# STC12C5A_LQFP44_Mini.net
KiCad netlist of a schematic drawn in Altium Designer
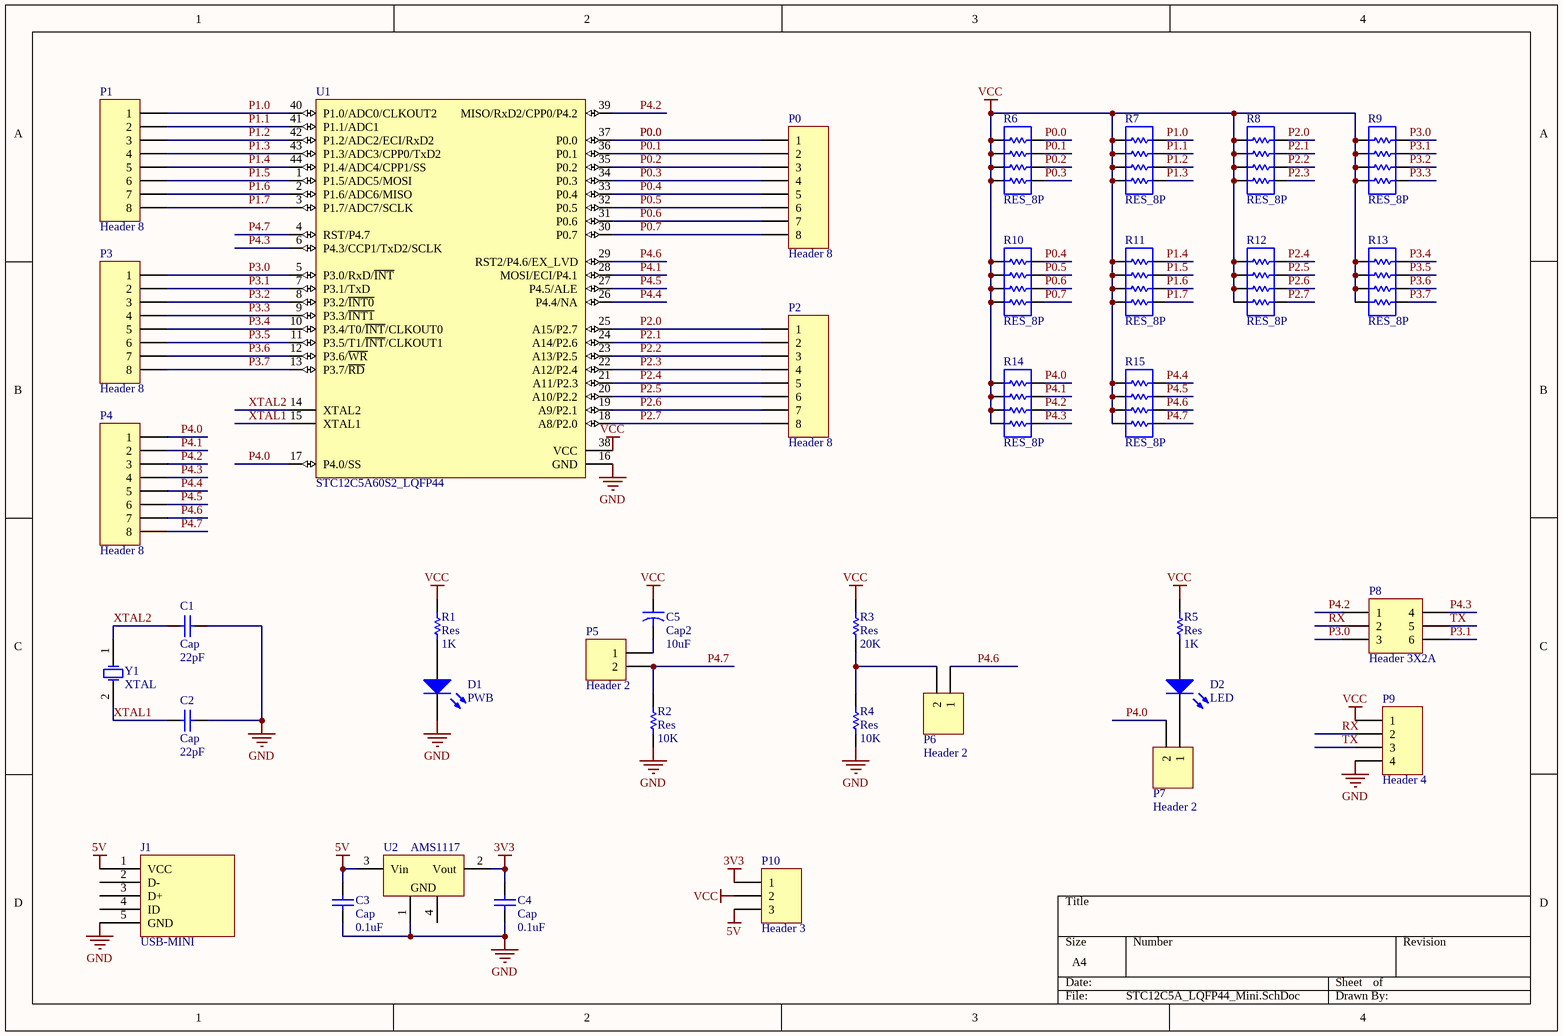
[diagram p0: STC12C5A_LQFP44_Mini.SchDoc]

(export (version "E")
  (design (tool "Eeschema 10.0.6"))
  (components
    (comp (ref "C1")
      (value "Cap")
      (footprint "C0805")
      (description "Capacitor")
      (fields (field (name "ALTIUM_VALUE") "22pF") (field (name "PUBLISHER") "Altium Limited"))
      (libsource (lib "Devices") (part "Cap"))
    )
    (comp (ref "C2")
      (value "Cap")
      (footprint "C0805")
      (description "Capacitor")
      (fields (field (name "ALTIUM_VALUE") "22pF") (field (name "PUBLISHER") "Altium Limited"))
      (libsource (lib "Devices") (part "Cap"))
    )
    (comp (ref "C3")
      (value "Cap")
      (footprint "C0805")
      (description "Capacitor")
      (fields (field (name "ALTIUM_VALUE") "0.1uF") (field (name "PUBLISHER") "Altium Limited"))
      (libsource (lib "Devices") (part "Cap"))
    )
    (comp (ref "C4")
      (value "Cap")
      (footprint "C0805")
      (description "Capacitor")
      (fields (field (name "ALTIUM_VALUE") "0.1uF") (field (name "PUBLISHER") "Altium Limited"))
      (libsource (lib "Devices") (part "Cap"))
    )
    (comp (ref "C5")
      (value "Cap2")
      (footprint "CAP-4.2")
      (description "Capacitor")
      (fields (field (name "ALTIUM_VALUE") "10uF") (field (name "PUBLISHER") "Altium Limited"))
      (libsource (lib "Devices") (part "Cap2"))
    )
    (comp (ref "D1")
      (value "PWB")
      (footprint "C0805")
      (description "发光二极管")
      (libsource (lib "Devices") (part "LED-2P"))
    )
    (comp (ref "D2")
      (value "LED")
      (footprint "C0805")
      (description "发光二极管")
      (libsource (lib "Devices") (part "LED-2P"))
    )
    (comp (ref "J1")
      (value "USB-MINI")
      (footprint "USB-MINI-A-SM")
      (libsource (lib "Connectors") (part "USB-MINI"))
    )
    (comp (ref "P0")
      (value "Header 8")
      (footprint "HDR1X8")
      (description "Header, 8-Pin")
      (fields (field (name "PUBLISHER") "Altium Limited"))
      (libsource (lib "") (part "Header 8_1"))
    )
    (comp (ref "P1")
      (value "Header 8")
      (footprint "HDR1X8")
      (description "Header, 8-Pin")
      (fields (field (name "PUBLISHER") "Altium Limited"))
      (libsource (lib "Connectors") (part "Header 8"))
    )
    (comp (ref "P2")
      (value "Header 8")
      (footprint "HDR1X8")
      (description "Header, 8-Pin")
      (fields (field (name "PUBLISHER") "Altium Limited"))
      (libsource (lib "") (part "Header 8_1"))
    )
    (comp (ref "P3")
      (value "Header 8")
      (footprint "HDR1X8")
      (description "Header, 8-Pin")
      (fields (field (name "PUBLISHER") "Altium Limited"))
      (libsource (lib "Connectors") (part "Header 8"))
    )
    (comp (ref "P4")
      (value "Header 8")
      (footprint "HDR1X8")
      (description "Header, 8-Pin")
      (fields (field (name "PUBLISHER") "Altium Limited"))
      (libsource (lib "Connectors") (part "Header 8"))
    )
    (comp (ref "P5")
      (value "Header 2")
      (footprint "HDR1X2")
      (description "Header, 2-Pin")
      (fields (field (name "PUBLISHER") "Altium Limited"))
      (libsource (lib "Connectors") (part "Header 2"))
    )
    (comp (ref "P6")
      (value "Header 2")
      (footprint "HDR1X2")
      (description "Header, 2-Pin")
      (fields (field (name "PUBLISHER") "Altium Limited"))
      (libsource (lib "Connectors") (part "Header 2"))
    )
    (comp (ref "P7")
      (value "Header 2")
      (footprint "HDR1X2")
      (description "Header, 2-Pin")
      (fields (field (name "PUBLISHER") "Altium Limited"))
      (libsource (lib "Connectors") (part "Header 2"))
    )
    (comp (ref "P8")
      (value "Header 3X2A")
      (footprint "HDR2X3_CEN")
      (description "Header, 3-Pin, Dual row")
      (fields (field (name "PUBLISHER") "Altium Limited"))
      (libsource (lib "Connectors") (part "Header 3X2A"))
    )
    (comp (ref "P9")
      (value "Header 4")
      (footprint "HDR1X4")
      (description "Header, 4-Pin")
      (fields (field (name "PUBLISHER") "Altium Limited"))
      (libsource (lib "Connectors") (part "Header 4"))
    )
    (comp (ref "P10")
      (value "Header 3")
      (footprint "HDR1X3")
      (description "Header, 3-Pin")
      (fields (field (name "PUBLISHER") "Altium Limited"))
      (libsource (lib "Connectors") (part "Header 3"))
    )
    (comp (ref "R1")
      (value "Res")
      (footprint "0805")
      (description "Resistor")
      (fields (field (name "ALTIUM_VALUE") "1K") (field (name "PUBLISHER") "Altium Limited"))
      (libsource (lib "Devices") (part "Res"))
    )
    (comp (ref "R2")
      (value "Res")
      (footprint "0805")
      (description "Resistor")
      (fields (field (name "ALTIUM_VALUE") "10K") (field (name "PUBLISHER") "Altium Limited"))
      (libsource (lib "Devices") (part "Res"))
    )
    (comp (ref "R3")
      (value "Res")
      (footprint "0805")
      (description "Resistor")
      (fields (field (name "ALTIUM_VALUE") "20K") (field (name "PUBLISHER") "Altium Limited"))
      (libsource (lib "Devices") (part "Res"))
    )
    (comp (ref "R4")
      (value "Res")
      (footprint "0805")
      (description "Resistor")
      (fields (field (name "ALTIUM_VALUE") "10K") (field (name "PUBLISHER") "Altium Limited"))
      (libsource (lib "Devices") (part "Res"))
    )
    (comp (ref "R5")
      (value "Res")
      (footprint "0805")
      (description "Resistor")
      (fields (field (name "ALTIUM_VALUE") "1K") (field (name "PUBLISHER") "Altium Limited"))
      (libsource (lib "Devices") (part "Res"))
    )
    (comp (ref "R6")
      (value "RES_8P")
      (footprint "RES_8P_0603")
      (description "贴片排阻")
      (libsource (lib "Devices") (part "RES_8P"))
    )
    (comp (ref "R7")
      (value "RES_8P")
      (footprint "RES_8P_0603")
      (description "贴片排阻")
      (libsource (lib "Devices") (part "RES_8P"))
    )
    (comp (ref "R8")
      (value "RES_8P")
      (footprint "RES_8P_0603")
      (description "贴片排阻")
      (libsource (lib "Devices") (part "RES_8P"))
    )
    (comp (ref "R9")
      (value "RES_8P")
      (footprint "RES_8P_0603")
      (description "贴片排阻")
      (libsource (lib "Devices") (part "RES_8P"))
    )
    (comp (ref "R10")
      (value "RES_8P")
      (footprint "RES_8P_0603")
      (description "贴片排阻")
      (libsource (lib "Devices") (part "RES_8P"))
    )
    (comp (ref "R11")
      (value "RES_8P")
      (footprint "RES_8P_0603")
      (description "贴片排阻")
      (libsource (lib "Devices") (part "RES_8P"))
    )
    (comp (ref "R12")
      (value "RES_8P")
      (footprint "RES_8P_0603")
      (description "贴片排阻")
      (libsource (lib "Devices") (part "RES_8P"))
    )
    (comp (ref "R13")
      (value "RES_8P")
      (footprint "RES_8P_0603")
      (description "贴片排阻")
      (libsource (lib "Devices") (part "RES_8P"))
    )
    (comp (ref "R14")
      (value "RES_8P")
      (footprint "RES_8P_0603")
      (description "贴片排阻")
      (libsource (lib "Devices") (part "RES_8P"))
    )
    (comp (ref "R15")
      (value "RES_8P")
      (footprint "RES_8P_0603")
      (description "贴片排阻")
      (libsource (lib "Devices") (part "RES_8P"))
    )
    (comp (ref "U1")
      (value "STC12C5A60S2_LQFP44")
      (footprint "LQFP44")
      (description "增强型8051单片机")
      (libsource (lib "STC") (part "STC12C5A60S2_LQFP44"))
    )
    (comp (ref "U2")
      (value "AMS1117")
      (footprint "SOT-223")
      (description "低压稳压器-1A")
      (libsource (lib "IC") (part "AMS1117"))
    )
    (comp (ref "Y1")
      (value "XTAL")
      (footprint "XTAL1")
      (description "Crystal Oscillator")
      (fields (field (name "PUBLISHER") "Altium Limited"))
      (libsource (lib "Miscellaneous Devices") (part "XTAL"))
    )
  )
  (nets
    (net (code "1") (name "/P0.0") (class "Default")
      (node (ref "P0") (pin "1") (pinfunction "1_1") (pintype "passive"))
      (node (ref "R6") (pin "2") (pinfunction "2_2") (pintype "passive"))
      (node (ref "U1") (pin "37") (pinfunction "P0.0_37") (pintype "bidirectional"))
    )
    (net (code "2") (name "/P0.1") (class "Default")
      (node (ref "P0") (pin "2") (pinfunction "2_2") (pintype "passive"))
      (node (ref "R6") (pin "4") (pinfunction "4_4") (pintype "passive"))
      (node (ref "U1") (pin "36") (pinfunction "P0.1_36") (pintype "bidirectional"))
    )
    (net (code "3") (name "/P0.2") (class "Default")
      (node (ref "P0") (pin "3") (pinfunction "3_3") (pintype "passive"))
      (node (ref "R6") (pin "6") (pinfunction "6_6") (pintype "passive"))
      (node (ref "U1") (pin "35") (pinfunction "P0.2_35") (pintype "bidirectional"))
    )
    (net (code "4") (name "/P0.3") (class "Default")
      (node (ref "P0") (pin "4") (pinfunction "4_4") (pintype "passive"))
      (node (ref "R6") (pin "8") (pinfunction "8_8") (pintype "passive"))
      (node (ref "U1") (pin "34") (pinfunction "P0.3_34") (pintype "bidirectional"))
    )
    (net (code "5") (name "/P0.4") (class "Default")
      (node (ref "P0") (pin "5") (pinfunction "5_5") (pintype "passive"))
      (node (ref "R10") (pin "2") (pinfunction "2_2") (pintype "passive"))
      (node (ref "U1") (pin "33") (pinfunction "P0.4_33") (pintype "bidirectional"))
    )
    (net (code "6") (name "/P0.5") (class "Default")
      (node (ref "P0") (pin "6") (pinfunction "6_6") (pintype "passive"))
      (node (ref "R10") (pin "4") (pinfunction "4_4") (pintype "passive"))
      (node (ref "U1") (pin "32") (pinfunction "P0.5_32") (pintype "bidirectional"))
    )
    (net (code "7") (name "/P0.6") (class "Default")
      (node (ref "P0") (pin "7") (pinfunction "7_7") (pintype "passive"))
      (node (ref "R10") (pin "6") (pinfunction "6_6") (pintype "passive"))
      (node (ref "U1") (pin "31") (pinfunction "P0.6_31") (pintype "bidirectional"))
    )
    (net (code "8") (name "/P0.7") (class "Default")
      (node (ref "P0") (pin "8") (pinfunction "8_8") (pintype "passive"))
      (node (ref "R10") (pin "8") (pinfunction "8_8") (pintype "passive"))
      (node (ref "U1") (pin "30") (pinfunction "P0.7_30") (pintype "bidirectional"))
    )
    (net (code "9") (name "/P1.0") (class "Default")
      (node (ref "P1") (pin "1") (pinfunction "1_1") (pintype "passive"))
      (node (ref "R7") (pin "2") (pinfunction "2_2") (pintype "passive"))
      (node (ref "U1") (pin "40") (pinfunction "P1.0/ADC0/CLKOUT2_40") (pintype "bidirectional"))
    )
    (net (code "10") (name "/P1.1") (class "Default")
      (node (ref "P1") (pin "2") (pinfunction "2_2") (pintype "passive"))
      (node (ref "R7") (pin "4") (pinfunction "4_4") (pintype "passive"))
      (node (ref "U1") (pin "41") (pinfunction "P1.1/ADC1_41") (pintype "bidirectional"))
    )
    (net (code "11") (name "/P1.2") (class "Default")
      (node (ref "P1") (pin "3") (pinfunction "3_3") (pintype "passive"))
      (node (ref "R7") (pin "6") (pinfunction "6_6") (pintype "passive"))
      (node (ref "U1") (pin "42") (pinfunction "P1.2/ADC2/ECI/RxD2_42") (pintype "bidirectional"))
    )
    (net (code "12") (name "/P1.3") (class "Default")
      (node (ref "P1") (pin "4") (pinfunction "4_4") (pintype "passive"))
      (node (ref "R7") (pin "8") (pinfunction "8_8") (pintype "passive"))
      (node (ref "U1") (pin "43") (pinfunction "P1.3/ADC3/CPP0/TxD2_43") (pintype "bidirectional"))
    )
    (net (code "13") (name "/P1.4") (class "Default")
      (node (ref "P1") (pin "5") (pinfunction "5_5") (pintype "passive"))
      (node (ref "R11") (pin "2") (pinfunction "2_2") (pintype "passive"))
      (node (ref "U1") (pin "44") (pinfunction "P1.4/ADC4/CPP1/SS_44") (pintype "bidirectional"))
    )
    (net (code "14") (name "/P1.5") (class "Default")
      (node (ref "P1") (pin "6") (pinfunction "6_6") (pintype "passive"))
      (node (ref "R11") (pin "4") (pinfunction "4_4") (pintype "passive"))
      (node (ref "U1") (pin "1") (pinfunction "P1.5/ADC5/MOSI_1") (pintype "bidirectional"))
    )
    (net (code "15") (name "/P1.6") (class "Default")
      (node (ref "P1") (pin "7") (pinfunction "7_7") (pintype "passive"))
      (node (ref "R11") (pin "6") (pinfunction "6_6") (pintype "passive"))
      (node (ref "U1") (pin "2") (pinfunction "P1.6/ADC6/MISO_2") (pintype "bidirectional"))
    )
    (net (code "16") (name "/P1.7") (class "Default")
      (node (ref "P1") (pin "8") (pinfunction "8_8") (pintype "passive"))
      (node (ref "R11") (pin "8") (pinfunction "8_8") (pintype "passive"))
      (node (ref "U1") (pin "3") (pinfunction "P1.7/ADC7/SCLK_3") (pintype "bidirectional"))
    )
    (net (code "17") (name "/P2.0") (class "Default")
      (node (ref "P2") (pin "1") (pinfunction "1_1") (pintype "passive"))
      (node (ref "R8") (pin "2") (pinfunction "2_2") (pintype "passive"))
      (node (ref "U1") (pin "25") (pinfunction "A15/P2.7_25") (pintype "bidirectional"))
    )
    (net (code "18") (name "/P2.1") (class "Default")
      (node (ref "P2") (pin "2") (pinfunction "2_2") (pintype "passive"))
      (node (ref "R8") (pin "4") (pinfunction "4_4") (pintype "passive"))
      (node (ref "U1") (pin "24") (pinfunction "A14/P2.6_24") (pintype "bidirectional"))
    )
    (net (code "19") (name "/P2.2") (class "Default")
      (node (ref "P2") (pin "3") (pinfunction "3_3") (pintype "passive"))
      (node (ref "R8") (pin "6") (pinfunction "6_6") (pintype "passive"))
      (node (ref "U1") (pin "23") (pinfunction "A13/P2.5_23") (pintype "bidirectional"))
    )
    (net (code "20") (name "/P2.3") (class "Default")
      (node (ref "P2") (pin "4") (pinfunction "4_4") (pintype "passive"))
      (node (ref "R8") (pin "8") (pinfunction "8_8") (pintype "passive"))
      (node (ref "U1") (pin "22") (pinfunction "A12/P2.4_22") (pintype "bidirectional"))
    )
    (net (code "21") (name "/P2.4") (class "Default")
      (node (ref "P2") (pin "5") (pinfunction "5_5") (pintype "passive"))
      (node (ref "R12") (pin "2") (pinfunction "2_2") (pintype "passive"))
      (node (ref "U1") (pin "21") (pinfunction "A11/P2.3_21") (pintype "bidirectional"))
    )
    (net (code "22") (name "/P2.5") (class "Default")
      (node (ref "P2") (pin "6") (pinfunction "6_6") (pintype "passive"))
      (node (ref "R12") (pin "4") (pinfunction "4_4") (pintype "passive"))
      (node (ref "U1") (pin "20") (pinfunction "A10/P2.2_20") (pintype "bidirectional"))
    )
    (net (code "23") (name "/P2.6") (class "Default")
      (node (ref "P2") (pin "7") (pinfunction "7_7") (pintype "passive"))
      (node (ref "R12") (pin "6") (pinfunction "6_6") (pintype "passive"))
      (node (ref "U1") (pin "19") (pinfunction "A9/P2.1_19") (pintype "bidirectional"))
    )
    (net (code "24") (name "/P2.7") (class "Default")
      (node (ref "P2") (pin "8") (pinfunction "8_8") (pintype "passive"))
      (node (ref "R12") (pin "8") (pinfunction "8_8") (pintype "passive"))
      (node (ref "U1") (pin "18") (pinfunction "A8/P2.0_18") (pintype "bidirectional"))
    )
    (net (code "25") (name "/P3.0") (class "Default")
      (node (ref "P3") (pin "1") (pinfunction "1_1") (pintype "passive"))
      (node (ref "P8") (pin "3") (pinfunction "3_3") (pintype "passive"))
      (node (ref "R9") (pin "2") (pinfunction "2_2") (pintype "passive"))
      (node (ref "U1") (pin "5") (pinfunction "P3.0/RxD/~{INT}_5") (pintype "bidirectional"))
    )
    (net (code "26") (name "/P3.1") (class "Default")
      (node (ref "P3") (pin "2") (pinfunction "2_2") (pintype "passive"))
      (node (ref "P8") (pin "6") (pinfunction "6_6") (pintype "passive"))
      (node (ref "R9") (pin "4") (pinfunction "4_4") (pintype "passive"))
      (node (ref "U1") (pin "7") (pinfunction "P3.1/TxD_7") (pintype "bidirectional"))
    )
    (net (code "27") (name "/P3.2") (class "Default")
      (node (ref "P3") (pin "3") (pinfunction "3_3") (pintype "passive"))
      (node (ref "R9") (pin "6") (pinfunction "6_6") (pintype "passive"))
      (node (ref "U1") (pin "8") (pinfunction "P3.2/~{INT0}_8") (pintype "bidirectional"))
    )
    (net (code "28") (name "/P3.3") (class "Default")
      (node (ref "P3") (pin "4") (pinfunction "4_4") (pintype "passive"))
      (node (ref "R9") (pin "8") (pinfunction "8_8") (pintype "passive"))
      (node (ref "U1") (pin "9") (pinfunction "P3.3/~{INT1}_9") (pintype "bidirectional"))
    )
    (net (code "29") (name "/P3.4") (class "Default")
      (node (ref "P3") (pin "5") (pinfunction "5_5") (pintype "passive"))
      (node (ref "R13") (pin "2") (pinfunction "2_2") (pintype "passive"))
      (node (ref "U1") (pin "10") (pinfunction "P3.4/T0/~{INT}/CLKOUT0_10") (pintype "bidirectional"))
    )
    (net (code "30") (name "/P3.5") (class "Default")
      (node (ref "P3") (pin "6") (pinfunction "6_6") (pintype "passive"))
      (node (ref "R13") (pin "4") (pinfunction "4_4") (pintype "passive"))
      (node (ref "U1") (pin "11") (pinfunction "P3.5/T1/~{INT}/CLKOUT1_11") (pintype "bidirectional"))
    )
    (net (code "31") (name "/P3.6") (class "Default")
      (node (ref "P3") (pin "7") (pinfunction "7_7") (pintype "passive"))
      (node (ref "R13") (pin "6") (pinfunction "6_6") (pintype "passive"))
      (node (ref "U1") (pin "12") (pinfunction "P3.6/~{WR}_12") (pintype "bidirectional"))
    )
    (net (code "32") (name "/P3.7") (class "Default")
      (node (ref "P3") (pin "8") (pinfunction "8_8") (pintype "passive"))
      (node (ref "R13") (pin "8") (pinfunction "8_8") (pintype "passive"))
      (node (ref "U1") (pin "13") (pinfunction "P3.7/~{RD}_13") (pintype "bidirectional"))
    )
    (net (code "33") (name "/P4.0") (class "Default")
      (node (ref "P4") (pin "1") (pinfunction "1_1") (pintype "passive"))
      (node (ref "P7") (pin "2") (pinfunction "2_2") (pintype "passive"))
      (node (ref "R14") (pin "2") (pinfunction "2_2") (pintype "passive"))
      (node (ref "U1") (pin "17") (pinfunction "P4.0/SS_17") (pintype "bidirectional"))
    )
    (net (code "34") (name "/P4.1") (class "Default")
      (node (ref "P4") (pin "2") (pinfunction "2_2") (pintype "passive"))
      (node (ref "R14") (pin "4") (pinfunction "4_4") (pintype "passive"))
      (node (ref "U1") (pin "28") (pinfunction "MOSI/ECI/P4.1_28") (pintype "bidirectional"))
    )
    (net (code "35") (name "/P4.2") (class "Default")
      (node (ref "P4") (pin "3") (pinfunction "3_3") (pintype "passive"))
      (node (ref "P8") (pin "1") (pinfunction "1_1") (pintype "passive"))
      (node (ref "R14") (pin "6") (pinfunction "6_6") (pintype "passive"))
      (node (ref "U1") (pin "39") (pinfunction "MISO/RxD2/CPP0/P4.2_39") (pintype "bidirectional"))
    )
    (net (code "36") (name "/P4.3") (class "Default")
      (node (ref "P4") (pin "4") (pinfunction "4_4") (pintype "passive"))
      (node (ref "P8") (pin "4") (pinfunction "4_4") (pintype "passive"))
      (node (ref "R14") (pin "8") (pinfunction "8_8") (pintype "passive"))
      (node (ref "U1") (pin "6") (pinfunction "P4.3/CCP1/TxD2/SCLK_6") (pintype "bidirectional"))
    )
    (net (code "37") (name "/P4.4") (class "Default")
      (node (ref "P4") (pin "5") (pinfunction "5_5") (pintype "passive"))
      (node (ref "R15") (pin "2") (pinfunction "2_2") (pintype "passive"))
      (node (ref "U1") (pin "26") (pinfunction "P4.4/NA_26") (pintype "bidirectional"))
    )
    (net (code "38") (name "/P4.5") (class "Default")
      (node (ref "P4") (pin "6") (pinfunction "6_6") (pintype "passive"))
      (node (ref "R15") (pin "4") (pinfunction "4_4") (pintype "passive"))
      (node (ref "U1") (pin "27") (pinfunction "P4.5/ALE_27") (pintype "bidirectional"))
    )
    (net (code "39") (name "/P4.6") (class "Default")
      (node (ref "P4") (pin "7") (pinfunction "7_7") (pintype "passive"))
      (node (ref "P6") (pin "1") (pinfunction "1_1") (pintype "passive"))
      (node (ref "R15") (pin "6") (pinfunction "6_6") (pintype "passive"))
      (node (ref "U1") (pin "29") (pinfunction "RST2/P4.6/EX_LVD_29") (pintype "bidirectional"))
    )
    (net (code "40") (name "/P4.7") (class "Default")
      (node (ref "P4") (pin "8") (pinfunction "8_8") (pintype "passive"))
      (node (ref "P5") (pin "2") (pinfunction "2_2") (pintype "passive"))
      (node (ref "R15") (pin "8") (pinfunction "8_8") (pintype "passive"))
      (node (ref "R2") (pin "2") (pinfunction "2_2") (pintype "passive"))
      (node (ref "U1") (pin "4") (pinfunction "RST/P4.7_4") (pintype "bidirectional"))
    )
    (net (code "41") (name "/RX") (class "Default")
      (node (ref "P8") (pin "2") (pinfunction "2_2") (pintype "passive"))
      (node (ref "P9") (pin "2") (pinfunction "2_2") (pintype "passive"))
    )
    (net (code "42") (name "/TX") (class "Default")
      (node (ref "P8") (pin "5") (pinfunction "5_5") (pintype "passive"))
      (node (ref "P9") (pin "3") (pinfunction "3_3") (pintype "passive"))
    )
    (net (code "43") (name "/XTAL1") (class "Default")
      (node (ref "C2") (pin "1") (pinfunction "1_1") (pintype "passive"))
      (node (ref "U1") (pin "15") (pinfunction "XTAL1_15") (pintype "passive"))
      (node (ref "Y1") (pin "2") (pinfunction "OSC2_2") (pintype "passive"))
    )
    (net (code "44") (name "/XTAL2") (class "Default")
      (node (ref "C1") (pin "1") (pinfunction "1_1") (pintype "passive"))
      (node (ref "U1") (pin "14") (pinfunction "XTAL2_14") (pintype "passive"))
      (node (ref "Y1") (pin "1") (pinfunction "OSC1_1") (pintype "passive"))
    )
    (net (code "45") (name "3V3") (class "Default")
      (node (ref "C4") (pin "2") (pinfunction "2_2") (pintype "passive"))
      (node (ref "P10") (pin "1") (pinfunction "1_1") (pintype "passive"))
      (node (ref "U2") (pin "2") (pinfunction "Vout_2") (pintype "passive"))
    )
    (net (code "46") (name "5V") (class "Default")
      (node (ref "C3") (pin "2") (pinfunction "2_2") (pintype "passive"))
      (node (ref "J1") (pin "1") (pinfunction "VCC_1") (pintype "power_in"))
      (node (ref "P10") (pin "3") (pinfunction "3_3") (pintype "passive"))
      (node (ref "U2") (pin "3") (pinfunction "Vin_3") (pintype "passive"))
    )
    (net (code "47") (name "GND") (class "Default")
      (node (ref "C1") (pin "2") (pinfunction "2_2") (pintype "passive"))
      (node (ref "C2") (pin "2") (pinfunction "2_2") (pintype "passive"))
      (node (ref "C3") (pin "1") (pinfunction "1_1") (pintype "passive"))
      (node (ref "C4") (pin "1") (pinfunction "1_1") (pintype "passive"))
      (node (ref "D1") (pin "2") (pinfunction "K_2") (pintype "passive"))
      (node (ref "J1") (pin "5") (pinfunction "GND_5") (pintype "power_in"))
      (node (ref "P9") (pin "4") (pinfunction "4_4") (pintype "passive"))
      (node (ref "R2") (pin "1") (pinfunction "1_1") (pintype "passive"))
      (node (ref "R4") (pin "1") (pinfunction "1_1") (pintype "passive"))
      (node (ref "U1") (pin "16") (pinfunction "GND_16") (pintype "power_in"))
      (node (ref "U2") (pin "1") (pinfunction "GND_1") (pintype "passive"))
    )
    (net (code "48") (name "Net-(C5-Pad2)") (class "Default")
      (node (ref "C5") (pin "2") (pinfunction "2_2") (pintype "passive"))
      (node (ref "P5") (pin "1") (pinfunction "1_1") (pintype "passive"))
    )
    (net (code "49") (name "Net-(D1-A)") (class "Default")
      (node (ref "D1") (pin "1") (pinfunction "A_1") (pintype "passive"))
      (node (ref "R1") (pin "1") (pinfunction "1_1") (pintype "passive"))
    )
    (net (code "50") (name "Net-(D2-A)") (class "Default")
      (node (ref "D2") (pin "1") (pinfunction "A_1") (pintype "passive"))
      (node (ref "R5") (pin "1") (pinfunction "1_1") (pintype "passive"))
    )
    (net (code "51") (name "Net-(D2-K)") (class "Default")
      (node (ref "D2") (pin "2") (pinfunction "K_2") (pintype "passive"))
      (node (ref "P7") (pin "1") (pinfunction "1_1") (pintype "passive"))
    )
    (net (code "52") (name "Net-(P6-Pad2)") (class "Default")
      (node (ref "P6") (pin "2") (pinfunction "2_2") (pintype "passive"))
      (node (ref "R3") (pin "1") (pinfunction "1_1") (pintype "passive"))
      (node (ref "R4") (pin "2") (pinfunction "2_2") (pintype "passive"))
    )
    (net (code "53") (name "VCC") (class "Default")
      (node (ref "C5") (pin "1") (pinfunction "1_1") (pintype "passive"))
      (node (ref "P10") (pin "2") (pinfunction "2_2") (pintype "passive"))
      (node (ref "P9") (pin "1") (pinfunction "1_1") (pintype "passive"))
      (node (ref "R1") (pin "2") (pinfunction "2_2") (pintype "passive"))
      (node (ref "R10") (pin "1") (pinfunction "1_1") (pintype "passive"))
      (node (ref "R10") (pin "3") (pinfunction "3_3") (pintype "passive"))
      (node (ref "R10") (pin "5") (pinfunction "5_5") (pintype "passive"))
      (node (ref "R10") (pin "7") (pinfunction "7_7") (pintype "passive"))
      (node (ref "R11") (pin "1") (pinfunction "1_1") (pintype "passive"))
      (node (ref "R11") (pin "3") (pinfunction "3_3") (pintype "passive"))
      (node (ref "R11") (pin "5") (pinfunction "5_5") (pintype "passive"))
      (node (ref "R11") (pin "7") (pinfunction "7_7") (pintype "passive"))
      (node (ref "R12") (pin "1") (pinfunction "1_1") (pintype "passive"))
      (node (ref "R12") (pin "3") (pinfunction "3_3") (pintype "passive"))
      (node (ref "R12") (pin "5") (pinfunction "5_5") (pintype "passive"))
      (node (ref "R12") (pin "7") (pinfunction "7_7") (pintype "passive"))
      (node (ref "R13") (pin "1") (pinfunction "1_1") (pintype "passive"))
      (node (ref "R13") (pin "3") (pinfunction "3_3") (pintype "passive"))
      (node (ref "R13") (pin "5") (pinfunction "5_5") (pintype "passive"))
      (node (ref "R13") (pin "7") (pinfunction "7_7") (pintype "passive"))
      (node (ref "R14") (pin "1") (pinfunction "1_1") (pintype "passive"))
      (node (ref "R14") (pin "3") (pinfunction "3_3") (pintype "passive"))
      (node (ref "R14") (pin "5") (pinfunction "5_5") (pintype "passive"))
      (node (ref "R14") (pin "7") (pinfunction "7_7") (pintype "passive"))
      (node (ref "R15") (pin "1") (pinfunction "1_1") (pintype "passive"))
      (node (ref "R15") (pin "3") (pinfunction "3_3") (pintype "passive"))
      (node (ref "R15") (pin "5") (pinfunction "5_5") (pintype "passive"))
      (node (ref "R15") (pin "7") (pinfunction "7_7") (pintype "passive"))
      (node (ref "R3") (pin "2") (pinfunction "2_2") (pintype "passive"))
      (node (ref "R5") (pin "2") (pinfunction "2_2") (pintype "passive"))
      (node (ref "R6") (pin "1") (pinfunction "1_1") (pintype "passive"))
      (node (ref "R6") (pin "3") (pinfunction "3_3") (pintype "passive"))
      (node (ref "R6") (pin "5") (pinfunction "5_5") (pintype "passive"))
      (node (ref "R6") (pin "7") (pinfunction "7_7") (pintype "passive"))
      (node (ref "R7") (pin "1") (pinfunction "1_1") (pintype "passive"))
      (node (ref "R7") (pin "3") (pinfunction "3_3") (pintype "passive"))
      (node (ref "R7") (pin "5") (pinfunction "5_5") (pintype "passive"))
      (node (ref "R7") (pin "7") (pinfunction "7_7") (pintype "passive"))
      (node (ref "R8") (pin "1") (pinfunction "1_1") (pintype "passive"))
      (node (ref "R8") (pin "3") (pinfunction "3_3") (pintype "passive"))
      (node (ref "R8") (pin "5") (pinfunction "5_5") (pintype "passive"))
      (node (ref "R8") (pin "7") (pinfunction "7_7") (pintype "passive"))
      (node (ref "R9") (pin "1") (pinfunction "1_1") (pintype "passive"))
      (node (ref "R9") (pin "3") (pinfunction "3_3") (pintype "passive"))
      (node (ref "R9") (pin "5") (pinfunction "5_5") (pintype "passive"))
      (node (ref "R9") (pin "7") (pinfunction "7_7") (pintype "passive"))
      (node (ref "U1") (pin "38") (pinfunction "VCC_38") (pintype "power_in"))
    )
    (net (code "54") (name "unconnected-(J1-D+-Pad3)") (class "Default")
      (node (ref "J1") (pin "3") (pinfunction "D+_3") (pintype "passive"))
    )
    (net (code "55") (name "unconnected-(J1-D--Pad2)") (class "Default")
      (node (ref "J1") (pin "2") (pinfunction "D-_2") (pintype "passive"))
    )
    (net (code "56") (name "unconnected-(J1-ID-Pad4)") (class "Default")
      (node (ref "J1") (pin "4") (pinfunction "ID_4") (pintype "passive"))
    )
    (net (code "57") (name "unconnected-(U2-GND-Pad4)") (class "Default")
      (node (ref "U2") (pin "4") (pinfunction "GND_4") (pintype "passive"))
    )
  )
)
